# LiPo-Charger.net
KiCad netlist of a schematic drawn in EAGLE
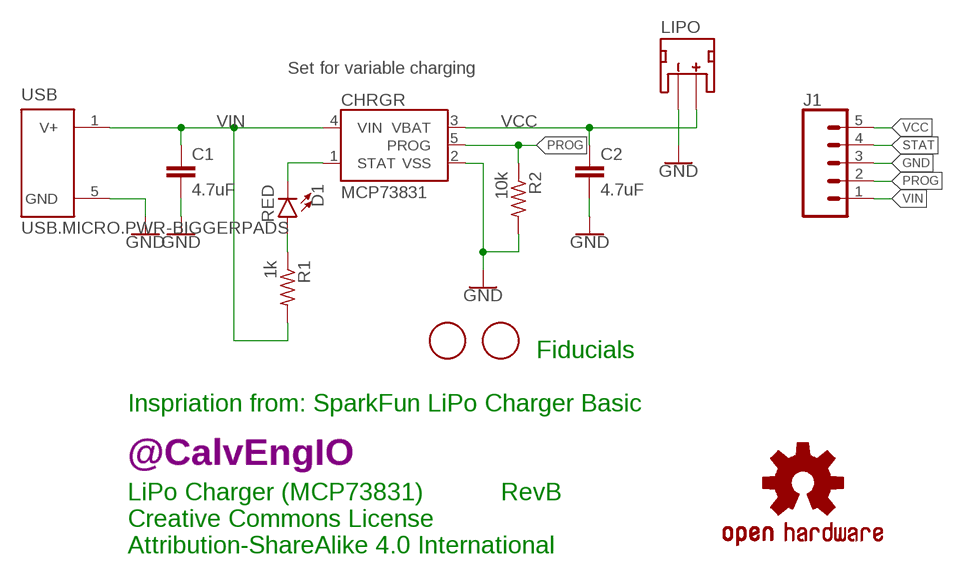
[diagram p0: schematic, sheet 1]

(export (version "E")
  (design (tool "Eeschema 10.0.6"))
  (components
    (comp (ref "C1")
      (value "4.7uF")
      (footprint "eagle-import:C0603")
      (libsource (lib "eagle-import") (part "CAPACITOR0603"))
    )
    (comp (ref "C2")
      (value "4.7uF")
      (footprint "eagle-import:C0603")
      (libsource (lib "eagle-import") (part "CAPACITOR0603"))
    )
    (comp (ref "CHRGR")
      (value "MCP73831")
      (footprint "eagle-import:SOT23-5")
      (libsource (lib "eagle-import") (part "MCP73831"))
    )
    (comp (ref "D1")
      (value "RED")
      (footprint "eagle-import:LED-0603")
      (libsource (lib "eagle-import") (part "LED0603"))
    )
    (comp (ref "J1")
      (value "CONN_05")
      (footprint "eagle-import:1X05")
      (libsource (lib "eagle-import") (part "CONN_05"))
    )
    (comp (ref "JP3")
      (value "FIDUCIAL")
      (footprint "eagle-import:FIDUCIAL_1MM")
      (libsource (lib "eagle-import") (part "FIDUCIAL"))
    )
    (comp (ref "JP4")
      (value "FIDUCIAL")
      (footprint "eagle-import:FIDUCIAL_1MM")
      (libsource (lib "eagle-import") (part "FIDUCIAL"))
    )
    (comp (ref "LIPO")
      (value "JST_2MM_MALE")
      (footprint "eagle-import:JST-2-SMD")
      (libsource (lib "eagle-import") (part "JST_2MM_MALE"))
    )
    (comp (ref "LOGO1")
      (value "OSHW-LOGOS")
      (footprint "eagle-import:OSHW-LOGO-S")
      (libsource (lib "eagle-import") (part "OSHW-LOGOS"))
    )
    (comp (ref "R1")
      (value "1k")
      (footprint "eagle-import:R0402")
      (libsource (lib "eagle-import") (part "RESISTOR0402"))
    )
    (comp (ref "R2")
      (value "10k")
      (footprint "eagle-import:R0402")
      (libsource (lib "eagle-import") (part "RESISTOR0402"))
    )
    (comp (ref "U$1")
      (value "CALVENGIO_HANDLEHANDLE.08")
      (footprint "eagle-import:CALVENGIO_HANDLE.08")
      (libsource (lib "eagle-import") (part "CALVENGIO_HANDLEHANDLE.08"))
    )
    (comp (ref "USB")
      (value "USB.MICRO.PWR-BIGGERPADS")
      (footprint "eagle-import:USB-MICRO-01.BIGGERPADS.PWR")
      (libsource (lib "eagle-import") (part "USB.MICRO.PWR-BIGGERPADS"))
    )
  )
  (nets
    (net (code "1") (name "GND") (class "Default")
      (node (ref "C1") (pin "2") (pinfunction "2_2") (pintype "passive"))
      (node (ref "C2") (pin "2") (pinfunction "2_2") (pintype "passive"))
      (node (ref "CHRGR") (pin "2") (pinfunction "VSS_2") (pintype "power_in"))
      (node (ref "J1") (pin "3") (pinfunction "3_3") (pintype "passive"))
      (node (ref "LIPO") (pin "1") (pinfunction "-_1") (pintype "bidirectional"))
      (node (ref "R2") (pin "2") (pinfunction "2_2") (pintype "passive"))
      (node (ref "USB") (pin "5") (pinfunction "GND_5") (pintype "bidirectional"))
    )
    (net (code "2") (name "Net-(D1-PadA)") (class "Default")
      (node (ref "D1") (pin "A") (pinfunction "A_A") (pintype "passive"))
      (node (ref "R1") (pin "1") (pinfunction "1_1") (pintype "passive"))
    )
    (net (code "3") (name "PROG") (class "Default")
      (node (ref "CHRGR") (pin "5") (pinfunction "PROG_5") (pintype "input"))
      (node (ref "J1") (pin "2") (pinfunction "2_2") (pintype "passive"))
      (node (ref "R2") (pin "1") (pinfunction "1_1") (pintype "passive"))
    )
    (net (code "4") (name "STAT") (class "Default")
      (node (ref "CHRGR") (pin "1") (pinfunction "STAT_1") (pintype "output"))
      (node (ref "D1") (pin "C") (pinfunction "C_C") (pintype "passive"))
      (node (ref "J1") (pin "4") (pinfunction "4_4") (pintype "passive"))
    )
    (net (code "5") (name "VCC") (class "Default")
      (node (ref "C2") (pin "1") (pinfunction "1_1") (pintype "passive"))
      (node (ref "CHRGR") (pin "3") (pinfunction "VBAT_3") (pintype "power_in"))
      (node (ref "J1") (pin "5") (pinfunction "5_5") (pintype "passive"))
      (node (ref "LIPO") (pin "2") (pinfunction "+_2") (pintype "bidirectional"))
    )
    (net (code "6") (name "VIN") (class "Default")
      (node (ref "C1") (pin "1") (pinfunction "1_1") (pintype "passive"))
      (node (ref "CHRGR") (pin "4") (pinfunction "VIN_4") (pintype "power_in"))
      (node (ref "J1") (pin "1") (pinfunction "1_1") (pintype "passive"))
      (node (ref "R1") (pin "2") (pinfunction "2_2") (pintype "passive"))
      (node (ref "USB") (pin "1") (pinfunction "V+_1") (pintype "bidirectional"))
    )
    (net (code "7") (name "unconnected-(LIPO-PAD1-PadNC1)") (class "Default")
      (node (ref "LIPO") (pin "NC1") (pinfunction "PAD1_NC1") (pintype "bidirectional"))
    )
    (net (code "8") (name "unconnected-(LIPO-PAD2-PadNC2)") (class "Default")
      (node (ref "LIPO") (pin "NC2") (pinfunction "PAD2_NC2") (pintype "bidirectional"))
    )
  )
)
